# Qwiic_FM_Transceiver_Si4721.net
KiCad netlist of a schematic drawn in EAGLE
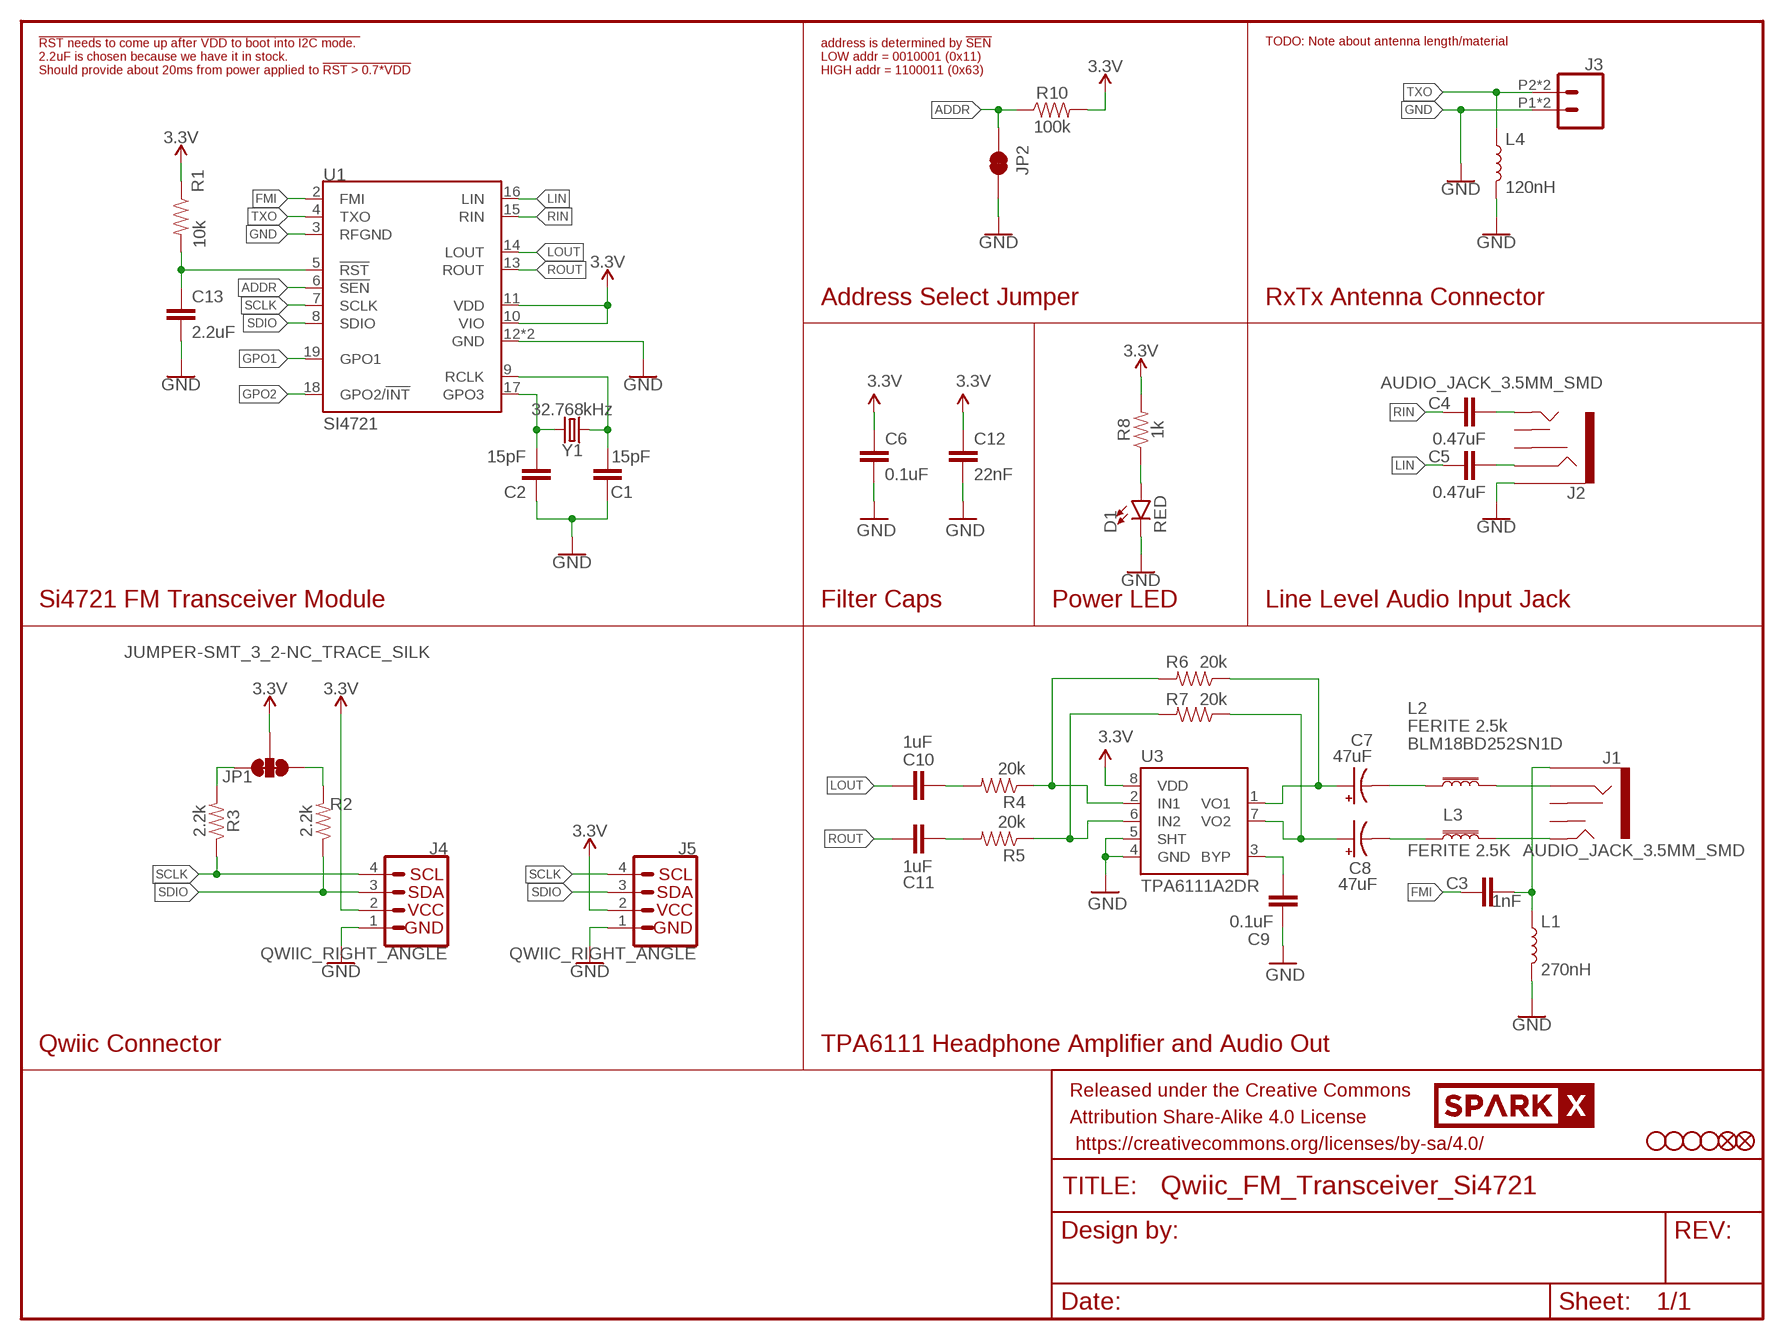
[diagram p0: schematic, sheet 1]

(export (version "E")
  (design (tool "Eeschema 10.0.6"))
  (components
    (comp (ref "C1")
      (value "15pF")
      (footprint "eagle-import:0603")
      (libsource (lib "eagle-import") (part "15PF-0603-50V-5%"))
    )
    (comp (ref "C2")
      (value "15pF")
      (footprint "eagle-import:0603")
      (libsource (lib "eagle-import") (part "15PF-0603-50V-5%"))
    )
    (comp (ref "C3")
      (value "1nF")
      (footprint "eagle-import:0603")
      (libsource (lib "eagle-import") (part "1.0NF/1000PF-0603-50V-10%"))
    )
    (comp (ref "C4")
      (value "0.47uF")
      (footprint "eagle-import:0603")
      (libsource (lib "eagle-import") (part "CAP-0603"))
    )
    (comp (ref "C5")
      (value "0.47uF")
      (footprint "eagle-import:0603")
      (libsource (lib "eagle-import") (part "CAP-0603"))
    )
    (comp (ref "C6")
      (value "0.1uF")
      (footprint "eagle-import:0603")
      (libsource (lib "eagle-import") (part "0.1UF-0603-25V-(+80/-20%)"))
    )
    (comp (ref "C7")
      (value "47uF")
      (footprint "eagle-import:EIA3528")
      (libsource (lib "eagle-import") (part "47UF-POLAR-EIA3528-10V-10%"))
    )
    (comp (ref "C8")
      (value "47uF")
      (footprint "eagle-import:EIA3528")
      (libsource (lib "eagle-import") (part "47UF-POLAR-EIA3528-10V-10%"))
    )
    (comp (ref "C9")
      (value "0.1uF")
      (footprint "eagle-import:0603")
      (libsource (lib "eagle-import") (part "0.1UF-0603-25V-(+80/-20%)"))
    )
    (comp (ref "C10")
      (value "1uF")
      (footprint "eagle-import:0603-CAP")
      (libsource (lib "eagle-import") (part "1.0UF-16V-10%(0603)"))
    )
    (comp (ref "C11")
      (value "1uF")
      (footprint "eagle-import:0603-CAP")
      (libsource (lib "eagle-import") (part "1.0UF-16V-10%(0603)"))
    )
    (comp (ref "C12")
      (value "22nF")
      (footprint "eagle-import:0603")
      (libsource (lib "eagle-import") (part "22NF/22,000PF-0603-50V-10%"))
    )
    (comp (ref "C13")
      (value "2.2uF")
      (footprint "eagle-import:0603")
      (libsource (lib "eagle-import") (part "2.2UF-0603-10V-20%"))
    )
    (comp (ref "D1")
      (value "RED")
      (footprint "eagle-import:LED-0603")
      (libsource (lib "eagle-import") (part "LED-RED0603"))
    )
    (comp (ref "FD1")
      (value "FIDUCIAL0.2MM")
      (footprint "eagle-import:FIDUCIAL-0.2MM")
      (libsource (lib "eagle-import") (part "FIDUCIAL0.2MM"))
    )
    (comp (ref "FD2")
      (value "FIDUCIAL0.2MM")
      (footprint "eagle-import:FIDUCIAL-0.2MM")
      (libsource (lib "eagle-import") (part "FIDUCIAL0.2MM"))
    )
    (comp (ref "FRAME1")
      (value "FRAME-LETTER")
      (footprint "eagle-import:CREATIVE_COMMONS")
      (libsource (lib "eagle-import") (part "FRAME-LETTER"))
    )
    (comp (ref "H1")
      (value "STAND-OFF")
      (footprint "eagle-import:STAND-OFF")
      (libsource (lib "eagle-import") (part "STAND-OFF"))
    )
    (comp (ref "H2")
      (value "STAND-OFF")
      (footprint "eagle-import:STAND-OFF")
      (libsource (lib "eagle-import") (part "STAND-OFF"))
    )
    (comp (ref "H3")
      (value "STAND-OFF")
      (footprint "eagle-import:STAND-OFF")
      (libsource (lib "eagle-import") (part "STAND-OFF"))
    )
    (comp (ref "H4")
      (value "STAND-OFF")
      (footprint "eagle-import:STAND-OFF")
      (libsource (lib "eagle-import") (part "STAND-OFF"))
    )
    (comp (ref "J1")
      (value "AUDIO_JACK_3.5MM_SMD")
      (footprint "eagle-import:AUDIO-JACK-3.5MM-SMD")
      (libsource (lib "eagle-import") (part "AUDIO_JACK_3.5MM_SMD"))
    )
    (comp (ref "J2")
      (value "AUDIO_JACK_3.5MM_SMD")
      (footprint "eagle-import:AUDIO-JACK-3.5MM-SMD")
      (libsource (lib "eagle-import") (part "AUDIO_JACK_3.5MM_SMD"))
    )
    (comp (ref "J3")
      (value "CONN_02SMALL_POKEHOME")
      (footprint "eagle-import:1X02_POKEHOME")
      (libsource (lib "eagle-import") (part "CONN_02SMALL_POKEHOME"))
    )
    (comp (ref "J4")
      (value "QWIIC_RIGHT_ANGLE")
      (footprint "eagle-import:JST04_1MM_RA")
      (libsource (lib "eagle-import") (part "QWIIC_CONNECTORJS-1MM"))
    )
    (comp (ref "J5")
      (value "QWIIC_RIGHT_ANGLE")
      (footprint "eagle-import:JST04_1MM_RA")
      (libsource (lib "eagle-import") (part "QWIIC_CONNECTORJS-1MM"))
    )
    (comp (ref "JP1")
      (value "JUMPER-SMT_3_2-NC_TRACE_SILK")
      (footprint "eagle-import:SMT-JUMPER_3_2-NC_TRACE_SILK")
      (libsource (lib "eagle-import") (part "JUMPER-SMT_3_2-NC_TRACE_SILK"))
    )
    (comp (ref "JP2")
      (value "JUMPER-SMT_2_NC_TRACE_SILK")
      (footprint "eagle-import:SMT-JUMPER_2_NC_TRACE_SILK")
      (libsource (lib "eagle-import") (part "JUMPER-SMT_2_NC_TRACE_SILK"))
    )
    (comp (ref "L1")
      (value "270nH")
      (footprint "eagle-import:0603")
      (libsource (lib "eagle-import") (part "INDUCTOR-0603-15NH"))
    )
    (comp (ref "L2")
      (value "FERITE 2.5k")
      (footprint "eagle-import:0603")
      (libsource (lib "eagle-import") (part "FERRITE_BEAD-0603"))
    )
    (comp (ref "L3")
      (value "FERITE 2.5K")
      (footprint "eagle-import:0603")
      (libsource (lib "eagle-import") (part "FERRITE_BEAD-0603"))
    )
    (comp (ref "L4")
      (value "120nH")
      (footprint "eagle-import:0603")
      (libsource (lib "eagle-import") (part "INDUCTOR-0603-15NH"))
    )
    (comp (ref "R1")
      (value "10k")
      (footprint "eagle-import:0603")
      (libsource (lib "eagle-import") (part "10KOHM-0603-1/10W-1%"))
    )
    (comp (ref "R2")
      (value "2.2k")
      (footprint "eagle-import:0603")
      (libsource (lib "eagle-import") (part "2.2KOHM-0603-1/10W-1%"))
    )
    (comp (ref "R3")
      (value "2.2k")
      (footprint "eagle-import:0603")
      (libsource (lib "eagle-import") (part "2.2KOHM-0603-1/10W-1%"))
    )
    (comp (ref "R4")
      (value "20k")
      (footprint "eagle-import:0603")
      (libsource (lib "eagle-import") (part "20KOHM-0603-1/10W-5%"))
    )
    (comp (ref "R5")
      (value "20k")
      (footprint "eagle-import:0603")
      (libsource (lib "eagle-import") (part "20KOHM-0603-1/10W-5%"))
    )
    (comp (ref "R6")
      (value "20k")
      (footprint "eagle-import:0603")
      (libsource (lib "eagle-import") (part "20KOHM-0603-1/10W-5%"))
    )
    (comp (ref "R7")
      (value "20k")
      (footprint "eagle-import:0603")
      (libsource (lib "eagle-import") (part "20KOHM-0603-1/10W-5%"))
    )
    (comp (ref "R8")
      (value "1k")
      (footprint "eagle-import:0603")
      (libsource (lib "eagle-import") (part "1KOHM-0603-1/10W-1%"))
    )
    (comp (ref "R10")
      (value "100k")
      (footprint "eagle-import:0603")
      (libsource (lib "eagle-import") (part "100KOHM-0603-1/10W-1%"))
    )
    (comp (ref "U$18")
      (value "SPARKX-LOGO4")
      (footprint "eagle-import:SPARKX-MEDIUM")
      (libsource (lib "eagle-import") (part "SPARKX-LOGO4"))
    )
    (comp (ref "U1")
      (value "SI4721")
      (footprint "eagle-import:QFN-20-3X3MM")
      (libsource (lib "eagle-import") (part "SI4721"))
    )
    (comp (ref "U3")
      (value "TPA6111A2DR")
      (footprint "eagle-import:SO08")
      (libsource (lib "eagle-import") (part "TPA6111SMD-T"))
    )
    (comp (ref "Y1")
      (value "32.768kHz")
      (footprint "eagle-import:CRYSTAL-SMD-3.2X1.5MM")
      (libsource (lib "eagle-import") (part "CRYSTAL-32.768KHZSMD-3.2X1.5"))
    )
  )
  (nets
    (net (code "1") (name "3.3V") (class "Default")
      (node (ref "C12") (pin "1") (pinfunction "1_1") (pintype "passive"))
      (node (ref "C6") (pin "1") (pinfunction "1_1") (pintype "passive"))
      (node (ref "J4") (pin "2") (pinfunction "2_2") (pintype "power_in"))
      (node (ref "J5") (pin "2") (pinfunction "2_2") (pintype "power_in"))
      (node (ref "JP1") (pin "2") (pinfunction "2_2") (pintype "passive"))
      (node (ref "R1") (pin "1") (pinfunction "1_1") (pintype "passive"))
      (node (ref "R10") (pin "2") (pinfunction "2_2") (pintype "passive"))
      (node (ref "R8") (pin "2") (pinfunction "2_2") (pintype "passive"))
      (node (ref "U1") (pin "10") (pinfunction "VIO_10") (pintype "power_in"))
      (node (ref "U1") (pin "11") (pinfunction "VDD_11") (pintype "power_in"))
      (node (ref "U3") (pin "8") (pinfunction "VDD_8") (pintype "bidirectional"))
    )
    (net (code "2") (name "ADDR") (class "Default")
      (node (ref "JP2") (pin "1") (pinfunction "1_1") (pintype "passive"))
      (node (ref "R10") (pin "1") (pinfunction "1_1") (pintype "passive"))
      (node (ref "U1") (pin "6") (pinfunction "~{SEN}_6") (pintype "input"))
    )
    (net (code "3") (name "FMI") (class "Default")
      (node (ref "C3") (pin "1") (pinfunction "1_1") (pintype "passive"))
      (node (ref "U1") (pin "2") (pinfunction "FMI_2") (pintype "input"))
    )
    (net (code "4") (name "GND") (class "Default")
      (node (ref "C1") (pin "1") (pinfunction "1_1") (pintype "passive"))
      (node (ref "C12") (pin "2") (pinfunction "2_2") (pintype "passive"))
      (node (ref "C13") (pin "2") (pinfunction "2_2") (pintype "passive"))
      (node (ref "C2") (pin "1") (pinfunction "1_1") (pintype "passive"))
      (node (ref "C6") (pin "2") (pinfunction "2_2") (pintype "passive"))
      (node (ref "C9") (pin "2") (pinfunction "2_2") (pintype "passive"))
      (node (ref "D1") (pin "C") (pinfunction "C_C") (pintype "passive"))
      (node (ref "J2") (pin "SLEEVE") (pinfunction "SLEEVE_SLEEVE") (pintype "bidirectional"))
      (node (ref "J3") (pin "P1") (pinfunction "1_P1") (pintype "passive"))
      (node (ref "J3") (pin "P3") (pinfunction "1_P3") (pintype "passive"))
      (node (ref "J4") (pin "1") (pinfunction "1_1") (pintype "power_in"))
      (node (ref "J5") (pin "1") (pinfunction "1_1") (pintype "power_in"))
      (node (ref "JP2") (pin "2") (pinfunction "2_2") (pintype "passive"))
      (node (ref "L1") (pin "2") (pinfunction "2_2") (pintype "passive"))
      (node (ref "L4") (pin "2") (pinfunction "2_2") (pintype "passive"))
      (node (ref "U1") (pin "12") (pinfunction "GND_12") (pintype "power_in"))
      (node (ref "U1") (pin "21") (pinfunction "GND_21") (pintype "power_in"))
      (node (ref "U1") (pin "3") (pinfunction "RFGND_3") (pintype "power_in"))
      (node (ref "U3") (pin "4") (pinfunction "GND_4") (pintype "bidirectional"))
      (node (ref "U3") (pin "5") (pinfunction "SHT_5") (pintype "bidirectional"))
    )
    (net (code "5") (name "GPO1") (class "Default")
      (node (ref "U1") (pin "19") (pinfunction "GPO1_19") (pintype "output"))
    )
    (net (code "6") (name "GPO2") (class "Default")
      (node (ref "U1") (pin "18") (pinfunction "GPO2/~{INT}_18") (pintype "output"))
    )
    (net (code "7") (name "LIN") (class "Default")
      (node (ref "C5") (pin "1") (pinfunction "1_1") (pintype "passive"))
      (node (ref "U1") (pin "16") (pinfunction "LIN_16") (pintype "input"))
    )
    (net (code "8") (name "LOUT") (class "Default")
      (node (ref "C10") (pin "1") (pinfunction "1_1") (pintype "passive"))
      (node (ref "U1") (pin "14") (pinfunction "LOUT_14") (pintype "output"))
    )
    (net (code "9") (name "Net-(C3-Pad2)") (class "Default")
      (node (ref "C3") (pin "2") (pinfunction "2_2") (pintype "passive"))
      (node (ref "J1") (pin "SLEEVE") (pinfunction "SLEEVE_SLEEVE") (pintype "bidirectional"))
      (node (ref "L1") (pin "1") (pinfunction "1_1") (pintype "passive"))
    )
    (net (code "10") (name "Net-(C4-Pad2)") (class "Default")
      (node (ref "C4") (pin "2") (pinfunction "2_2") (pintype "passive"))
      (node (ref "J2") (pin "TIP") (pinfunction "TIP_TIP") (pintype "bidirectional"))
    )
    (net (code "11") (name "Net-(C5-Pad2)") (class "Default")
      (node (ref "C5") (pin "2") (pinfunction "2_2") (pintype "passive"))
      (node (ref "J2") (pin "RING") (pinfunction "RING_RING") (pintype "bidirectional"))
    )
    (net (code "12") (name "Net-(C7-+)") (class "Default")
      (node (ref "C7") (pin "A") (pinfunction "+_A") (pintype "passive"))
      (node (ref "R6") (pin "1") (pinfunction "1_1") (pintype "passive"))
      (node (ref "U3") (pin "1") (pinfunction "VO1_1") (pintype "bidirectional"))
    )
    (net (code "13") (name "Net-(C7--)") (class "Default")
      (node (ref "C7") (pin "C") (pinfunction "-_C") (pintype "passive"))
      (node (ref "L2") (pin "1") (pinfunction "1_1") (pintype "passive"))
    )
    (net (code "14") (name "Net-(C8-+)") (class "Default")
      (node (ref "C8") (pin "A") (pinfunction "+_A") (pintype "passive"))
      (node (ref "R7") (pin "1") (pinfunction "1_1") (pintype "passive"))
      (node (ref "U3") (pin "7") (pinfunction "VO2_7") (pintype "bidirectional"))
    )
    (net (code "15") (name "Net-(C8--)") (class "Default")
      (node (ref "C8") (pin "C") (pinfunction "-_C") (pintype "passive"))
      (node (ref "L3") (pin "1") (pinfunction "1_1") (pintype "passive"))
    )
    (net (code "16") (name "Net-(C10-Pad2)") (class "Default")
      (node (ref "C10") (pin "2") (pinfunction "2_2") (pintype "passive"))
      (node (ref "R4") (pin "2") (pinfunction "2_2") (pintype "passive"))
    )
    (net (code "17") (name "Net-(C11-Pad2)") (class "Default")
      (node (ref "C11") (pin "2") (pinfunction "2_2") (pintype "passive"))
      (node (ref "R5") (pin "2") (pinfunction "2_2") (pintype "passive"))
    )
    (net (code "18") (name "Net-(D1-PadA)") (class "Default")
      (node (ref "D1") (pin "A") (pinfunction "A_A") (pintype "passive"))
      (node (ref "R8") (pin "1") (pinfunction "1_1") (pintype "passive"))
    )
    (net (code "19") (name "Net-(J1-PadRING)") (class "Default")
      (node (ref "J1") (pin "RING") (pinfunction "RING_RING") (pintype "bidirectional"))
      (node (ref "L2") (pin "2") (pinfunction "2_2") (pintype "passive"))
    )
    (net (code "20") (name "Net-(J1-PadTIP)") (class "Default")
      (node (ref "J1") (pin "TIP") (pinfunction "TIP_TIP") (pintype "bidirectional"))
      (node (ref "L3") (pin "2") (pinfunction "2_2") (pintype "passive"))
    )
    (net (code "21") (name "Net-(JP1-Pad1)") (class "Default")
      (node (ref "JP1") (pin "1") (pinfunction "1_1") (pintype "passive"))
      (node (ref "R3") (pin "2") (pinfunction "2_2") (pintype "passive"))
    )
    (net (code "22") (name "Net-(JP1-Pad3)") (class "Default")
      (node (ref "JP1") (pin "3") (pinfunction "3_3") (pintype "passive"))
      (node (ref "R2") (pin "2") (pinfunction "2_2") (pintype "passive"))
    )
    (net (code "23") (name "Net-(U1-GPO3)") (class "Default")
      (node (ref "C2") (pin "2") (pinfunction "2_2") (pintype "passive"))
      (node (ref "U1") (pin "17") (pinfunction "GPO3_17") (pintype "output"))
      (node (ref "Y1") (pin "P$2") (pinfunction "2_P$2") (pintype "passive"))
    )
    (net (code "24") (name "Net-(U1-RCLK)") (class "Default")
      (node (ref "C1") (pin "2") (pinfunction "2_2") (pintype "passive"))
      (node (ref "U1") (pin "9") (pinfunction "RCLK_9") (pintype "input"))
      (node (ref "Y1") (pin "P$1") (pinfunction "1_P$1") (pintype "passive"))
    )
    (net (code "25") (name "Net-(U1-~{RST})") (class "Default")
      (node (ref "C13") (pin "1") (pinfunction "1_1") (pintype "passive"))
      (node (ref "R1") (pin "2") (pinfunction "2_2") (pintype "passive"))
      (node (ref "U1") (pin "5") (pinfunction "~{RST}_5") (pintype "input"))
    )
    (net (code "26") (name "Net-(U3-BYP)") (class "Default")
      (node (ref "C9") (pin "1") (pinfunction "1_1") (pintype "passive"))
      (node (ref "U3") (pin "3") (pinfunction "BYP_3") (pintype "bidirectional"))
    )
    (net (code "27") (name "Net-(U3-IN1)") (class "Default")
      (node (ref "R4") (pin "1") (pinfunction "1_1") (pintype "passive"))
      (node (ref "R6") (pin "2") (pinfunction "2_2") (pintype "passive"))
      (node (ref "U3") (pin "2") (pinfunction "IN1_2") (pintype "bidirectional"))
    )
    (net (code "28") (name "Net-(U3-IN2)") (class "Default")
      (node (ref "R5") (pin "1") (pinfunction "1_1") (pintype "passive"))
      (node (ref "R7") (pin "2") (pinfunction "2_2") (pintype "passive"))
      (node (ref "U3") (pin "6") (pinfunction "IN2_6") (pintype "bidirectional"))
    )
    (net (code "29") (name "RIN") (class "Default")
      (node (ref "C4") (pin "1") (pinfunction "1_1") (pintype "passive"))
      (node (ref "U1") (pin "15") (pinfunction "RIN_15") (pintype "input"))
    )
    (net (code "30") (name "ROUT") (class "Default")
      (node (ref "C11") (pin "1") (pinfunction "1_1") (pintype "passive"))
      (node (ref "U1") (pin "13") (pinfunction "ROUT_13") (pintype "output"))
    )
    (net (code "31") (name "SCLK") (class "Default")
      (node (ref "J4") (pin "4") (pinfunction "4_4") (pintype "passive"))
      (node (ref "J5") (pin "4") (pinfunction "4_4") (pintype "passive"))
      (node (ref "R3") (pin "1") (pinfunction "1_1") (pintype "passive"))
      (node (ref "U1") (pin "7") (pinfunction "SCLK_7") (pintype "input"))
    )
    (net (code "32") (name "SDIO") (class "Default")
      (node (ref "J4") (pin "3") (pinfunction "3_3") (pintype "passive"))
      (node (ref "J5") (pin "3") (pinfunction "3_3") (pintype "passive"))
      (node (ref "R2") (pin "1") (pinfunction "1_1") (pintype "passive"))
      (node (ref "U1") (pin "8") (pinfunction "SDIO_8") (pintype "bidirectional"))
    )
    (net (code "33") (name "TXO") (class "Default")
      (node (ref "J3") (pin "P2") (pinfunction "2_P2") (pintype "passive"))
      (node (ref "J3") (pin "P4") (pinfunction "2_P4") (pintype "passive"))
      (node (ref "L4") (pin "1") (pinfunction "1_1") (pintype "passive"))
      (node (ref "U1") (pin "4") (pinfunction "TXO_4") (pintype "bidirectional"))
    )
    (net (code "34") (name "unconnected-(J1-PadRSH)") (class "Default")
      (node (ref "J1") (pin "RSH") (pinfunction "RSH_RSH") (pintype "bidirectional"))
    )
    (net (code "35") (name "unconnected-(J1-PadTSH)") (class "Default")
      (node (ref "J1") (pin "TSH") (pinfunction "TSH_TSH") (pintype "bidirectional"))
    )
    (net (code "36") (name "unconnected-(J2-PadRSH)") (class "Default")
      (node (ref "J2") (pin "RSH") (pinfunction "RSH_RSH") (pintype "bidirectional"))
    )
    (net (code "37") (name "unconnected-(J2-PadTSH)") (class "Default")
      (node (ref "J2") (pin "TSH") (pinfunction "TSH_TSH") (pintype "bidirectional"))
    )
  )
)
